# NinjaPCB-131202.net
KiCad netlist of a schematic drawn in EAGLE
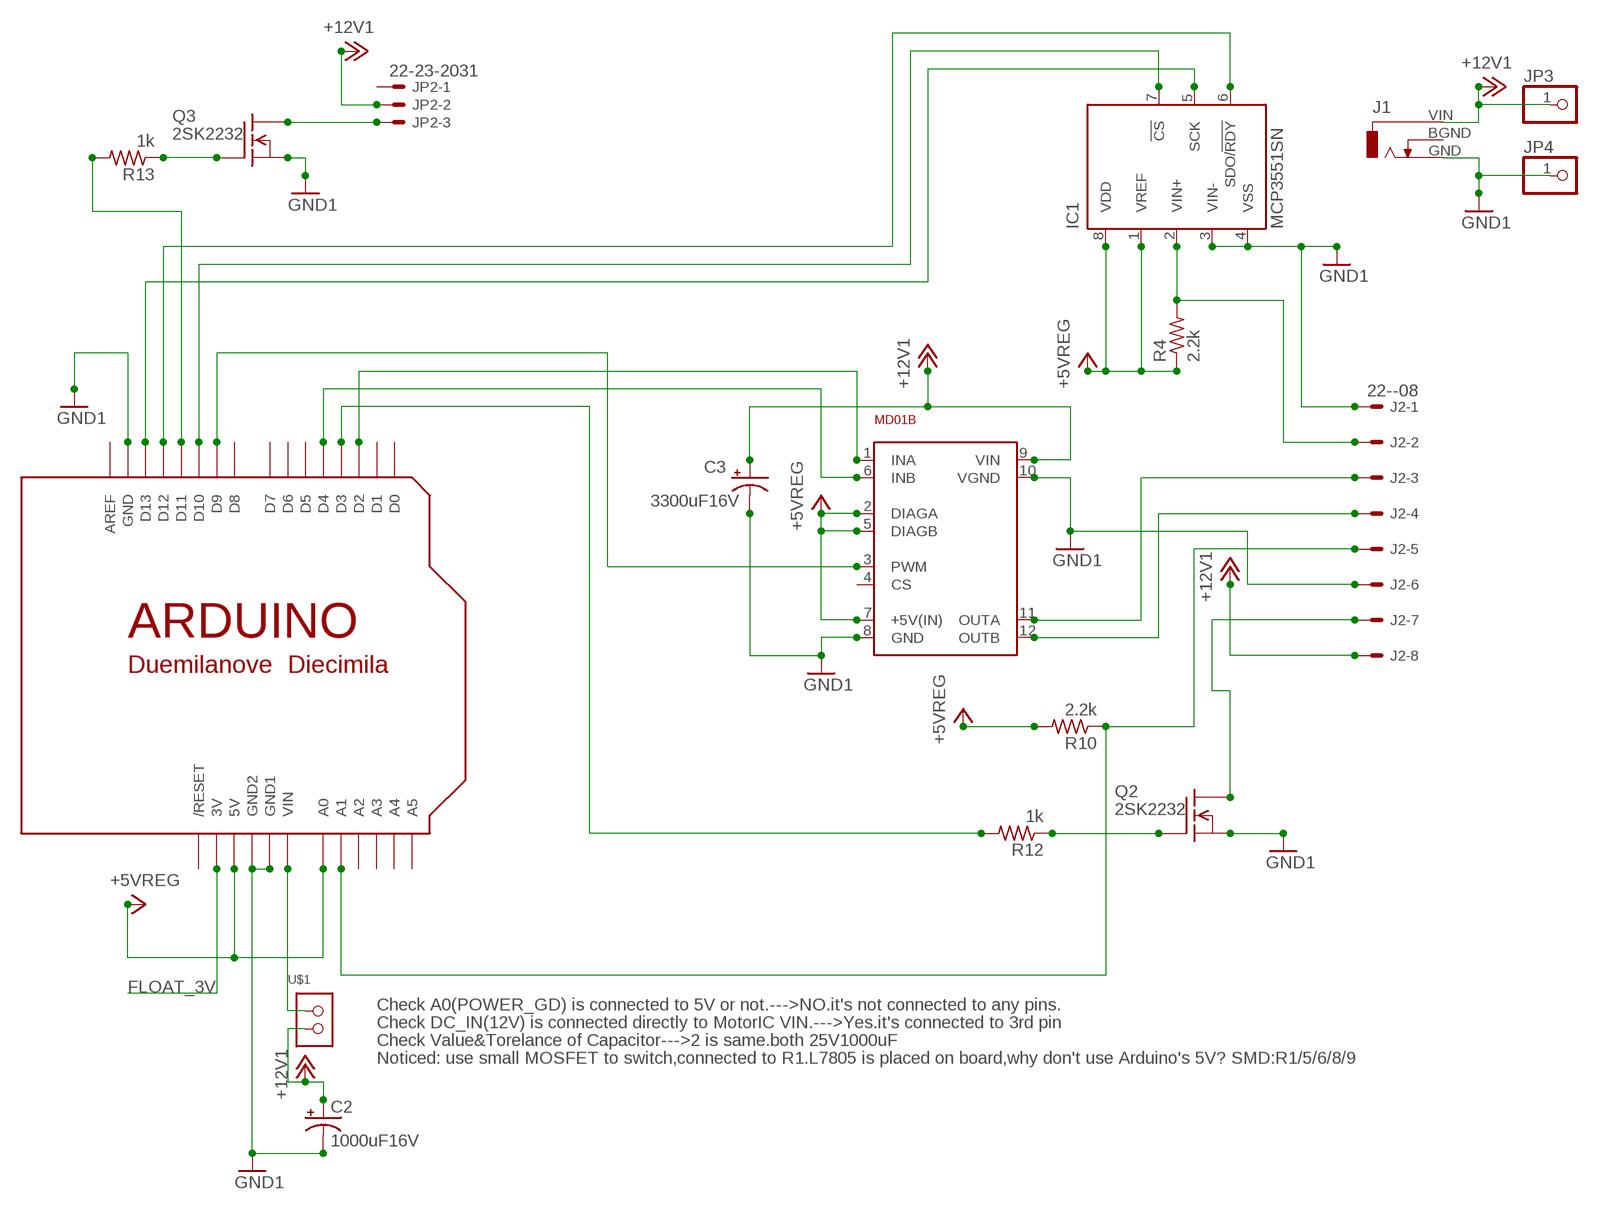
[diagram p0: schematic, sheet 1]

(export (version "E")
  (design (tool "Eeschema 10.0.6"))
  (components
    (comp (ref "C2")
      (value "1000uF16V")
      (footprint "eagle-import:E5-8,5")
      (libsource (lib "eagle-import") (part "CPOL-USE5-8.5"))
    )
    (comp (ref "C3")
      (value "3300uF16V")
      (footprint "eagle-import:E5-13")
      (libsource (lib "eagle-import") (part "CPOL-USE5-13"))
    )
    (comp (ref "IC1")
      (value "MCP3551SN")
      (footprint "eagle-import:SO-08")
      (fields (field (name "MPN") "MCP3551-E/SN"))
      (libsource (lib "eagle-import") (part "MCP355SN1"))
    )
    (comp (ref "J1")
      (value "DCJ0303")
      (footprint "eagle-import:DCJ0303")
      (libsource (lib "eagle-import") (part "DCJ0303"))
    )
    (comp (ref "J2")
      (value "22--08")
      (footprint "eagle-import:POLOLU-8-VERTICAL")
      (libsource (lib "eagle-import") (part "22-?-08"))
    )
    (comp (ref "JP2")
      (value "22-23-2031")
      (footprint "eagle-import:22-23-2031")
      (fields (field (name "MF") "MOLEX"))
      (libsource (lib "eagle-import") (part "22-23-2031"))
    )
    (comp (ref "JP3")
      (value "PINHD-1X1")
      (footprint "eagle-import:1X01")
      (libsource (lib "eagle-import") (part "PINHD-1X1"))
    )
    (comp (ref "JP4")
      (value "PINHD-1X1")
      (footprint "eagle-import:1X01")
      (libsource (lib "eagle-import") (part "PINHD-1X1"))
    )
    (comp (ref "MD01B")
      (value "VNH3SP30+4PINN")
      (footprint "eagle-import:VNH3SP30+4PIN_NOHOLES")
      (libsource (lib "eagle-import") (part "VNH3SP30+4PINN"))
    )
    (comp (ref "Q2")
      (value "2SK2232")
      (footprint "eagle-import:TO202")
      (libsource (lib "eagle-import") (part "BSS97"))
    )
    (comp (ref "Q3")
      (value "2SK2232")
      (footprint "eagle-import:TO202")
      (libsource (lib "eagle-import") (part "BSS97"))
    )
    (comp (ref "R4")
      (value "2.2k")
      (footprint "eagle-import:0207_10")
      (libsource (lib "eagle-import") (part "R-US_0207/10"))
    )
    (comp (ref "R10")
      (value "2.2k")
      (footprint "eagle-import:0207_10")
      (libsource (lib "eagle-import") (part "R-US_0207/10"))
    )
    (comp (ref "R12")
      (value "1k")
      (footprint "eagle-import:0207_10")
      (libsource (lib "eagle-import") (part "R-US_0207/10"))
    )
    (comp (ref "R13")
      (value "1k")
      (footprint "eagle-import:0207_10")
      (libsource (lib "eagle-import") (part "R-US_0207/10"))
    )
    (comp (ref "U$1")
      (value "1X02")
      (footprint "eagle-import:1X02_1.1_UNSIGNED")
      (libsource (lib "eagle-import") (part "1X02"))
    )
    (comp (ref "U$3")
      (value "Arduino UNO")
      (footprint "eagle-import:ARDUINO-NOSILK")
      (libsource (lib "eagle-import") (part "ARDUINONS"))
    )
  )
  (nets
    (net (code "1") (name "+5VREG") (class "Default")
      (node (ref "IC1") (pin "1") (pinfunction "VREF_1") (pintype "input"))
      (node (ref "IC1") (pin "8") (pinfunction "VDD_8") (pintype "power_in"))
      (node (ref "MD01B") (pin "2") (pinfunction "DIAGA_2") (pintype "passive"))
      (node (ref "MD01B") (pin "5") (pinfunction "DIAGB_5") (pintype "passive"))
      (node (ref "MD01B") (pin "7") (pinfunction "+5V(IN)_7") (pintype "power_in"))
      (node (ref "R10") (pin "2") (pinfunction "2_2") (pintype "passive"))
      (node (ref "R4") (pin "1") (pinfunction "1_1") (pintype "passive"))
      (node (ref "U$3") (pin "5V") (pinfunction "5V_5V") (pintype "power_in"))
      (node (ref "U$3") (pin "A0") (pinfunction "A0_A0") (pintype "bidirectional"))
    )
    (net (code "2") (name "+12V1") (class "Default")
      (node (ref "C2") (pin "+") (pinfunction "+_+") (pintype "passive"))
      (node (ref "C3") (pin "+") (pinfunction "+_+") (pintype "passive"))
      (node (ref "J1") (pin "VIN") (pinfunction "VIN_VIN") (pintype "passive"))
      (node (ref "J2") (pin "8") (pinfunction "S_8") (pintype "passive"))
      (node (ref "JP2") (pin "2") (pinfunction "S_2") (pintype "passive"))
      (node (ref "JP3") (pin "1") (pinfunction "1_1") (pintype "passive"))
      (node (ref "MD01B") (pin "9") (pinfunction "VIN_9") (pintype "power_in"))
      (node (ref "U$1") (pin "2") (pinfunction "2_2") (pintype "passive"))
    )
    (net (code "3") (name "/FLOAT_3V") (class "Default")
      (node (ref "U$3") (pin "3V") (pinfunction "3V_3V") (pintype "power_in"))
    )
    (net (code "4") (name "GND1") (class "Default")
      (node (ref "C2") (pin "-") (pinfunction "-_-") (pintype "passive"))
      (node (ref "C3") (pin "-") (pinfunction "-_-") (pintype "passive"))
      (node (ref "IC1") (pin "3") (pinfunction "VIN-_3") (pintype "input"))
      (node (ref "IC1") (pin "4") (pinfunction "VSS_4") (pintype "power_in"))
      (node (ref "J1") (pin "GND") (pinfunction "GND_GND") (pintype "passive"))
      (node (ref "J2") (pin "1") (pinfunction "S_1") (pintype "passive"))
      (node (ref "J2") (pin "6") (pinfunction "S_6") (pintype "passive"))
      (node (ref "JP4") (pin "1") (pinfunction "1_1") (pintype "passive"))
      (node (ref "MD01B") (pin "10") (pinfunction "VGND_10") (pintype "power_in"))
      (node (ref "MD01B") (pin "8") (pinfunction "GND_8") (pintype "power_in"))
      (node (ref "Q2") (pin "1") (pinfunction "S_1") (pintype "passive"))
      (node (ref "Q3") (pin "1") (pinfunction "S_1") (pintype "passive"))
      (node (ref "U$3") (pin "GND") (pinfunction "GND_GND") (pintype "power_in"))
      (node (ref "U$3") (pin "GND1") (pinfunction "GND1_GND1") (pintype "power_in"))
      (node (ref "U$3") (pin "GND2") (pinfunction "GND2_GND2") (pintype "power_in"))
    )
    (net (code "5") (name "Net-(IC1-SCK)") (class "Default")
      (node (ref "IC1") (pin "5") (pinfunction "SCK_5") (pintype "input"))
      (node (ref "U$3") (pin "D13") (pinfunction "D13_D13") (pintype "bidirectional"))
    )
    (net (code "6") (name "Net-(IC1-SDO{slash}~{RDY})") (class "Default")
      (node (ref "IC1") (pin "6") (pinfunction "SDO/~{RDY}_6") (pintype "output"))
      (node (ref "U$3") (pin "D12") (pinfunction "D12_D12") (pintype "bidirectional"))
    )
    (net (code "7") (name "Net-(IC1-VIN+)") (class "Default")
      (node (ref "IC1") (pin "2") (pinfunction "VIN+_2") (pintype "input"))
      (node (ref "J2") (pin "2") (pinfunction "S_2") (pintype "passive"))
      (node (ref "R4") (pin "2") (pinfunction "2_2") (pintype "passive"))
    )
    (net (code "8") (name "Net-(IC1-~{CS})") (class "Default")
      (node (ref "IC1") (pin "7") (pinfunction "~{CS}_7") (pintype "input"))
      (node (ref "U$3") (pin "D10") (pinfunction "D10_D10") (pintype "bidirectional"))
    )
    (net (code "9") (name "Net-(J2C-S)") (class "Default")
      (node (ref "J2") (pin "3") (pinfunction "S_3") (pintype "passive"))
      (node (ref "MD01B") (pin "11") (pinfunction "OUTA_11") (pintype "passive"))
    )
    (net (code "10") (name "Net-(J2D-S)") (class "Default")
      (node (ref "J2") (pin "4") (pinfunction "S_4") (pintype "passive"))
      (node (ref "MD01B") (pin "12") (pinfunction "OUTB_12") (pintype "passive"))
    )
    (net (code "11") (name "Net-(J2E-S)") (class "Default")
      (node (ref "J2") (pin "5") (pinfunction "S_5") (pintype "passive"))
      (node (ref "R10") (pin "1") (pinfunction "1_1") (pintype "passive"))
      (node (ref "U$3") (pin "A1") (pinfunction "A1_A1") (pintype "bidirectional"))
    )
    (net (code "12") (name "Net-(J2G-S)") (class "Default")
      (node (ref "J2") (pin "7") (pinfunction "S_7") (pintype "passive"))
      (node (ref "Q2") (pin "2") (pinfunction "D_2") (pintype "passive"))
    )
    (net (code "13") (name "Net-(JP2C-S)") (class "Default")
      (node (ref "JP2") (pin "3") (pinfunction "S_3") (pintype "passive"))
      (node (ref "Q3") (pin "2") (pinfunction "D_2") (pintype "passive"))
    )
    (net (code "14") (name "Net-(MD01B-INA)") (class "Default")
      (node (ref "MD01B") (pin "1") (pinfunction "INA_1") (pintype "passive"))
      (node (ref "U$3") (pin "D2") (pinfunction "D2_D2") (pintype "bidirectional"))
    )
    (net (code "15") (name "Net-(MD01B-INB)") (class "Default")
      (node (ref "MD01B") (pin "6") (pinfunction "INB_6") (pintype "passive"))
      (node (ref "U$3") (pin "D4") (pinfunction "D4_D4") (pintype "bidirectional"))
    )
    (net (code "16") (name "Net-(MD01B-PWM)") (class "Default")
      (node (ref "MD01B") (pin "3") (pinfunction "PWM_3") (pintype "passive"))
      (node (ref "U$3") (pin "D9") (pinfunction "D9_D9") (pintype "bidirectional"))
    )
    (net (code "17") (name "Net-(Q2-G)") (class "Default")
      (node (ref "Q2") (pin "3") (pinfunction "G_3") (pintype "passive"))
      (node (ref "R12") (pin "1") (pinfunction "1_1") (pintype "passive"))
    )
    (net (code "18") (name "Net-(Q3-G)") (class "Default")
      (node (ref "Q3") (pin "3") (pinfunction "G_3") (pintype "passive"))
      (node (ref "R13") (pin "1") (pinfunction "1_1") (pintype "passive"))
    )
    (net (code "19") (name "Net-(R12-Pad2)") (class "Default")
      (node (ref "R12") (pin "2") (pinfunction "2_2") (pintype "passive"))
      (node (ref "U$3") (pin "D3") (pinfunction "D3_D3") (pintype "bidirectional"))
    )
    (net (code "20") (name "Net-(R13-Pad2)") (class "Default")
      (node (ref "R13") (pin "2") (pinfunction "2_2") (pintype "passive"))
      (node (ref "U$3") (pin "D11") (pinfunction "D11_D11") (pintype "bidirectional"))
    )
    (net (code "21") (name "Net-(U$1-Pad1)") (class "Default")
      (node (ref "U$1") (pin "1") (pinfunction "1_1") (pintype "passive"))
      (node (ref "U$3") (pin "VIN") (pinfunction "VIN_VIN") (pintype "power_in"))
    )
    (net (code "22") (name "unconnected-(J1-PadBGND)") (class "Default")
      (node (ref "J1") (pin "BGND") (pinfunction "BGND_BGND") (pintype "passive"))
    )
    (net (code "23") (name "unconnected-(JP2A-S-Pad1)") (class "Default")
      (node (ref "JP2") (pin "1") (pinfunction "S_1") (pintype "passive"))
    )
    (net (code "24") (name "unconnected-(MD01B-CS-Pad4)") (class "Default")
      (node (ref "MD01B") (pin "4") (pinfunction "CS_4") (pintype "passive"))
    )
    (net (code "25") (name "unconnected-(U$3-PadA2)") (class "Default")
      (node (ref "U$3") (pin "A2") (pinfunction "A2_A2") (pintype "bidirectional"))
    )
    (net (code "26") (name "unconnected-(U$3-PadA3)") (class "Default")
      (node (ref "U$3") (pin "A3") (pinfunction "A3_A3") (pintype "bidirectional"))
    )
    (net (code "27") (name "unconnected-(U$3-PadA4)") (class "Default")
      (node (ref "U$3") (pin "A4") (pinfunction "A4_A4") (pintype "bidirectional"))
    )
    (net (code "28") (name "unconnected-(U$3-PadA5)") (class "Default")
      (node (ref "U$3") (pin "A5") (pinfunction "A5_A5") (pintype "bidirectional"))
    )
    (net (code "29") (name "unconnected-(U$3-PadAREF)") (class "Default")
      (node (ref "U$3") (pin "AREF") (pinfunction "AREF_AREF") (pintype "bidirectional"))
    )
    (net (code "30") (name "unconnected-(U$3-PadD0)") (class "Default")
      (node (ref "U$3") (pin "D0") (pinfunction "D0_D0") (pintype "bidirectional"))
    )
    (net (code "31") (name "unconnected-(U$3-PadD1)") (class "Default")
      (node (ref "U$3") (pin "D1") (pinfunction "D1_D1") (pintype "bidirectional"))
    )
    (net (code "32") (name "unconnected-(U$3-PadD5)") (class "Default")
      (node (ref "U$3") (pin "D5") (pinfunction "D5_D5") (pintype "bidirectional"))
    )
    (net (code "33") (name "unconnected-(U$3-PadD6)") (class "Default")
      (node (ref "U$3") (pin "D6") (pinfunction "D6_D6") (pintype "bidirectional"))
    )
    (net (code "34") (name "unconnected-(U$3-PadD7)") (class "Default")
      (node (ref "U$3") (pin "D7") (pinfunction "D7_D7") (pintype "bidirectional"))
    )
    (net (code "35") (name "unconnected-(U$3-PadD8)") (class "Default")
      (node (ref "U$3") (pin "D8") (pinfunction "D8_D8") (pintype "bidirectional"))
    )
    (net (code "36") (name "unconnected-(U$3-{slash}RESET-PadRESET)") (class "Default")
      (node (ref "U$3") (pin "RESET") (pinfunction "/RESET_RESET") (pintype "bidirectional"))
    )
  )
)
